# HCMS-2975.net
KiCad netlist of a schematic drawn in Altium Designer
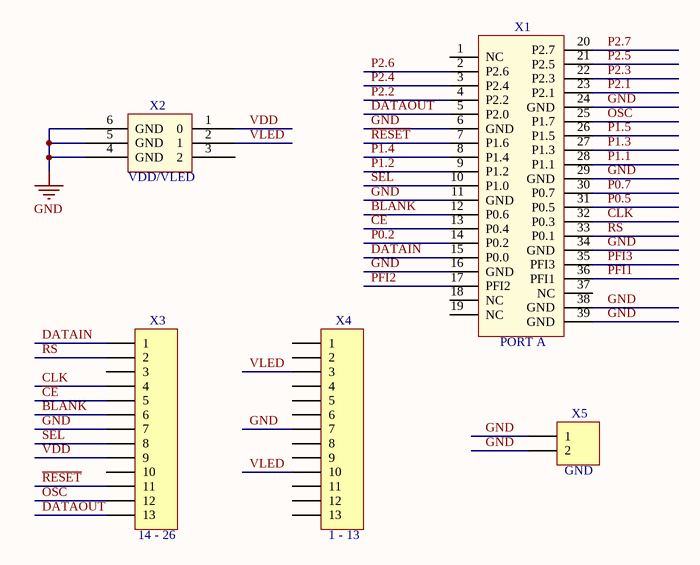
[diagram p0: HCMS-2975.SchDoc]

(export (version "E")
  (design (tool "Eeschema 10.0.6"))
  (components
    (comp (ref "X1")
      (value "PORT A")
      (footprint "CHEAP_CONN_FEMALE")
      (libsource (lib "Schlib") (part "CHEAP_CON_37_FEMALE"))
    )
    (comp (ref "X2") (value "VDD/VLED") (footprint "POWER") (libsource (lib "Schlib") (part "POWER")))
    (comp (ref "X3")
      (value "14 - 26")
      (footprint "HDR1X13")
      (description "Header, 13-Pin")
      (fields (field (name "PUBLISHER") "Altium Limited"))
      (libsource (lib "Miscellaneous Connectors") (part "Header 13"))
    )
    (comp (ref "X4")
      (value "1 - 13")
      (footprint "HDR1X13")
      (description "Header, 13-Pin")
      (fields (field (name "PUBLISHER") "Altium Limited"))
      (libsource (lib "Miscellaneous Connectors") (part "Header 13"))
    )
    (comp (ref "X5")
      (value "GND")
      (footprint "HDR1X2")
      (description "Header, 2-Pin")
      (fields (field (name "PUBLISHER") "Altium Limited"))
      (libsource (lib "Miscellaneous Connectors") (part "Header 2"))
    )
  )
  (nets
    (net (code "1") (name "/BLANK") (class "Default")
      (node (ref "X1") (pin "12") (pinfunction "P0.6_12") (pintype "passive"))
      (node (ref "X3") (pin "6") (pinfunction "6_6") (pintype "passive"))
    )
    (net (code "2") (name "/CLK") (class "Default")
      (node (ref "X1") (pin "32") (pinfunction "P0.3_32") (pintype "passive"))
      (node (ref "X3") (pin "4") (pinfunction "4_4") (pintype "passive"))
    )
    (net (code "3") (name "/DATAIN") (class "Default")
      (node (ref "X1") (pin "15") (pinfunction "P0.0_15") (pintype "passive"))
      (node (ref "X3") (pin "1") (pinfunction "1_1") (pintype "passive"))
    )
    (net (code "4") (name "/DATAOUT") (class "Default")
      (node (ref "X1") (pin "5") (pinfunction "P2.0_5") (pintype "passive"))
      (node (ref "X3") (pin "13") (pinfunction "13_13") (pintype "passive"))
    )
    (net (code "5") (name "/OSC") (class "Default")
      (node (ref "X1") (pin "25") (pinfunction "P1.7_25") (pintype "passive"))
      (node (ref "X3") (pin "12") (pinfunction "12_12") (pintype "passive"))
    )
    (net (code "6") (name "/P0.2") (class "Default")
      (node (ref "X1") (pin "14") (pinfunction "P0.2_14") (pintype "passive"))
    )
    (net (code "7") (name "/P0.5") (class "Default")
      (node (ref "X1") (pin "31") (pinfunction "P0.5_31") (pintype "passive"))
    )
    (net (code "8") (name "/P0.7") (class "Default")
      (node (ref "X1") (pin "30") (pinfunction "P0.7_30") (pintype "passive"))
    )
    (net (code "9") (name "/P1.1") (class "Default")
      (node (ref "X1") (pin "28") (pinfunction "P1.1_28") (pintype "passive"))
    )
    (net (code "10") (name "/P1.2") (class "Default")
      (node (ref "X1") (pin "9") (pinfunction "P1.2_9") (pintype "passive"))
    )
    (net (code "11") (name "/P1.3") (class "Default")
      (node (ref "X1") (pin "27") (pinfunction "P1.3_27") (pintype "passive"))
    )
    (net (code "12") (name "/P1.4") (class "Default")
      (node (ref "X1") (pin "8") (pinfunction "P1.4_8") (pintype "passive"))
    )
    (net (code "13") (name "/P1.5") (class "Default")
      (node (ref "X1") (pin "26") (pinfunction "P1.5_26") (pintype "passive"))
    )
    (net (code "14") (name "/P2.1") (class "Default")
      (node (ref "X1") (pin "23") (pinfunction "P2.1_23") (pintype "passive"))
    )
    (net (code "15") (name "/P2.2") (class "Default")
      (node (ref "X1") (pin "4") (pinfunction "P2.2_4") (pintype "passive"))
    )
    (net (code "16") (name "/P2.3") (class "Default")
      (node (ref "X1") (pin "22") (pinfunction "P2.3_22") (pintype "passive"))
    )
    (net (code "17") (name "/P2.4") (class "Default")
      (node (ref "X1") (pin "3") (pinfunction "P2.4_3") (pintype "passive"))
    )
    (net (code "18") (name "/P2.5") (class "Default")
      (node (ref "X1") (pin "21") (pinfunction "P2.5_21") (pintype "passive"))
    )
    (net (code "19") (name "/P2.6") (class "Default")
      (node (ref "X1") (pin "2") (pinfunction "P2.6_2") (pintype "passive"))
    )
    (net (code "20") (name "/P2.7") (class "Default")
      (node (ref "X1") (pin "20") (pinfunction "P2.7_20") (pintype "passive"))
    )
    (net (code "21") (name "/PFI1") (class "Default")
      (node (ref "X1") (pin "36") (pinfunction "PFI1_36") (pintype "passive"))
    )
    (net (code "22") (name "/PFI2") (class "Default")
      (node (ref "X1") (pin "17") (pinfunction "PFI2_17") (pintype "passive"))
    )
    (net (code "23") (name "/PFI3") (class "Default")
      (node (ref "X1") (pin "35") (pinfunction "PFI3_35") (pintype "passive"))
    )
    (net (code "24") (name "/RS") (class "Default")
      (node (ref "X1") (pin "33") (pinfunction "P0.1_33") (pintype "passive"))
      (node (ref "X3") (pin "2") (pinfunction "2_2") (pintype "passive"))
    )
    (net (code "25") (name "/SEL") (class "Default")
      (node (ref "X1") (pin "10") (pinfunction "P1.0_10") (pintype "passive"))
      (node (ref "X3") (pin "8") (pinfunction "8_8") (pintype "passive"))
    )
    (net (code "26") (name "/VDD") (class "Default")
      (node (ref "X2") (pin "1") (pinfunction "0_1") (pintype "passive"))
      (node (ref "X3") (pin "9") (pinfunction "9_9") (pintype "passive"))
    )
    (net (code "27") (name "/VLED") (class "Default")
      (node (ref "X2") (pin "2") (pinfunction "1_2") (pintype "passive"))
      (node (ref "X4") (pin "10") (pinfunction "10_10") (pintype "passive"))
      (node (ref "X4") (pin "3") (pinfunction "3_3") (pintype "passive"))
    )
    (net (code "28") (name "/~{CE}") (class "Default")
      (node (ref "X1") (pin "13") (pinfunction "P0.4_13") (pintype "passive"))
      (node (ref "X3") (pin "5") (pinfunction "5_5") (pintype "passive"))
    )
    (net (code "29") (name "/~{RESET}") (class "Default")
      (node (ref "X1") (pin "7") (pinfunction "P1.6_7") (pintype "passive"))
      (node (ref "X3") (pin "11") (pinfunction "11_11") (pintype "passive"))
    )
    (net (code "30") (name "GND") (class "Default")
      (node (ref "X1") (pin "11") (pinfunction "GND_11") (pintype "passive"))
      (node (ref "X1") (pin "16") (pinfunction "GND_16") (pintype "passive"))
      (node (ref "X1") (pin "24") (pinfunction "GND_24") (pintype "passive"))
      (node (ref "X1") (pin "29") (pinfunction "GND_29") (pintype "passive"))
      (node (ref "X1") (pin "34") (pinfunction "GND_34") (pintype "passive"))
      (node (ref "X1") (pin "38") (pinfunction "GND_38") (pintype "passive"))
      (node (ref "X1") (pin "39") (pinfunction "GND_39") (pintype "passive"))
      (node (ref "X1") (pin "6") (pinfunction "GND_6") (pintype "passive"))
      (node (ref "X2") (pin "4") (pinfunction "GND_4") (pintype "passive"))
      (node (ref "X2") (pin "5") (pinfunction "GND_5") (pintype "passive"))
      (node (ref "X2") (pin "6") (pinfunction "GND_6") (pintype "passive"))
      (node (ref "X3") (pin "7") (pinfunction "7_7") (pintype "passive"))
      (node (ref "X4") (pin "7") (pinfunction "7_7") (pintype "passive"))
      (node (ref "X5") (pin "1") (pinfunction "1_1") (pintype "passive"))
      (node (ref "X5") (pin "2") (pinfunction "2_2") (pintype "passive"))
    )
    (net (code "31") (name "unconnected-(X1-NC-Pad1)") (class "Default")
      (node (ref "X1") (pin "1") (pinfunction "NC_1") (pintype "passive"))
    )
    (net (code "32") (name "unconnected-(X1-NC-Pad18)") (class "Default")
      (node (ref "X1") (pin "18") (pinfunction "NC_18") (pintype "passive"))
    )
    (net (code "33") (name "unconnected-(X1-NC-Pad19)") (class "Default")
      (node (ref "X1") (pin "19") (pinfunction "NC_19") (pintype "passive"))
    )
    (net (code "34") (name "unconnected-(X1-NC-Pad37)") (class "Default")
      (node (ref "X1") (pin "37") (pinfunction "NC_37") (pintype "passive"))
    )
    (net (code "35") (name "unconnected-(X2-2-Pad3)") (class "Default")
      (node (ref "X2") (pin "3") (pinfunction "2_3") (pintype "passive"))
    )
    (net (code "36") (name "unconnected-(X3-Pad3)") (class "Default")
      (node (ref "X3") (pin "3") (pinfunction "3_3") (pintype "passive"))
    )
    (net (code "37") (name "unconnected-(X3-Pad10)") (class "Default")
      (node (ref "X3") (pin "10") (pinfunction "10_10") (pintype "passive"))
    )
    (net (code "38") (name "unconnected-(X4-Pad1)") (class "Default")
      (node (ref "X4") (pin "1") (pinfunction "1_1") (pintype "passive"))
    )
    (net (code "39") (name "unconnected-(X4-Pad2)") (class "Default")
      (node (ref "X4") (pin "2") (pinfunction "2_2") (pintype "passive"))
    )
    (net (code "40") (name "unconnected-(X4-Pad4)") (class "Default")
      (node (ref "X4") (pin "4") (pinfunction "4_4") (pintype "passive"))
    )
    (net (code "41") (name "unconnected-(X4-Pad5)") (class "Default")
      (node (ref "X4") (pin "5") (pinfunction "5_5") (pintype "passive"))
    )
    (net (code "42") (name "unconnected-(X4-Pad6)") (class "Default")
      (node (ref "X4") (pin "6") (pinfunction "6_6") (pintype "passive"))
    )
    (net (code "43") (name "unconnected-(X4-Pad8)") (class "Default")
      (node (ref "X4") (pin "8") (pinfunction "8_8") (pintype "passive"))
    )
    (net (code "44") (name "unconnected-(X4-Pad9)") (class "Default")
      (node (ref "X4") (pin "9") (pinfunction "9_9") (pintype "passive"))
    )
    (net (code "45") (name "unconnected-(X4-Pad11)") (class "Default")
      (node (ref "X4") (pin "11") (pinfunction "11_11") (pintype "passive"))
    )
    (net (code "46") (name "unconnected-(X4-Pad12)") (class "Default")
      (node (ref "X4") (pin "12") (pinfunction "12_12") (pintype "passive"))
    )
    (net (code "47") (name "unconnected-(X4-Pad13)") (class "Default")
      (node (ref "X4") (pin "13") (pinfunction "13_13") (pintype "passive"))
    )
  )
)
